# QSPI.net
KiCad netlist of a schematic drawn in Altium Designer
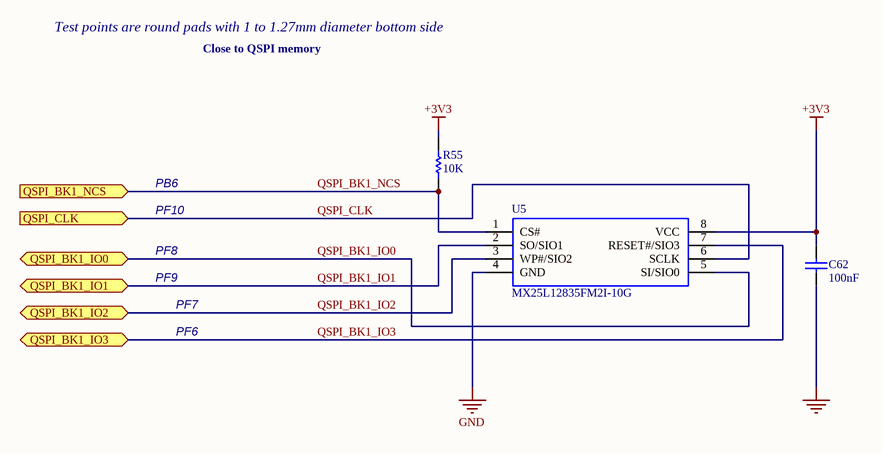
[diagram p0: QSPI.SchDoc]

(export (version "E")
  (design (tool "Eeschema 10.0.6"))
  (components
    (comp (ref "C62")
      (value "100nF")
      (footprint "CAP - 0402")
      (description "Capacitor")
      (fields (field (name "PUBLISHER") "Altium Limited"))
      (libsource (lib "Miscellaneous Devices") (part "Cap"))
    )
    (comp (ref "R55")
      (value "10K")
      (footprint "RES - 0402")
      (description "Resistor")
      (libsource (lib "MCD_TOOLS") (part "Res_10K_1%_0402"))
    )
    (comp (ref "U5")
      (value "MX25L12835FM2I-10G")
      (footprint "SOIC127P790X216-8N")
      (description "Macronix MX25L12835FM2I-10G 128Mbit Flash Memory; 3V, SOP, 8-Pin")
      (fields (field (name "RS PART NUMBER") "1703072"))
      (libsource (lib "MX25L12835FM2I-10G") (part "MX25L12835FM2I-10G"))
    )
  )
  (nets
    (net (code "1") (name "+3V3") (class "Default")
      (node (ref "C62") (pin "1") (pinfunction "1_1") (pintype "passive"))
      (node (ref "R55") (pin "2") (pinfunction "2_2") (pintype "passive"))
      (node (ref "U5") (pin "8") (pinfunction "VCC_8") (pintype "passive"))
    )
    (net (code "2") (name "/QSPI_BK1_IO0") (class "Default")
      (node (ref "U5") (pin "5") (pinfunction "SI/SIO0_5") (pintype "passive"))
    )
    (net (code "3") (name "/QSPI_BK1_IO1") (class "Default")
      (node (ref "U5") (pin "2") (pinfunction "SO/SIO1_2") (pintype "passive"))
    )
    (net (code "4") (name "/QSPI_BK1_IO2") (class "Default")
      (node (ref "U5") (pin "3") (pinfunction "WP#/SIO2_3") (pintype "passive"))
    )
    (net (code "5") (name "/QSPI_BK1_IO3") (class "Default")
      (node (ref "U5") (pin "7") (pinfunction "RESET#/SIO3_7") (pintype "passive"))
    )
    (net (code "6") (name "/QSPI_BK1_NCS") (class "Default")
      (node (ref "R55") (pin "1") (pinfunction "1_1") (pintype "passive"))
      (node (ref "U5") (pin "1") (pinfunction "CS#_1") (pintype "passive"))
    )
    (net (code "7") (name "/QSPI_CLK") (class "Default")
      (node (ref "U5") (pin "6") (pinfunction "SCLK_6") (pintype "passive"))
    )
    (net (code "8") (name "GND") (class "Default")
      (node (ref "C62") (pin "2") (pinfunction "2_2") (pintype "passive"))
      (node (ref "U5") (pin "4") (pinfunction "GND_4") (pintype "passive"))
    )
  )
)
